# nbedmbed_minipro.net
KiCad netlist of a schematic drawn in EAGLE
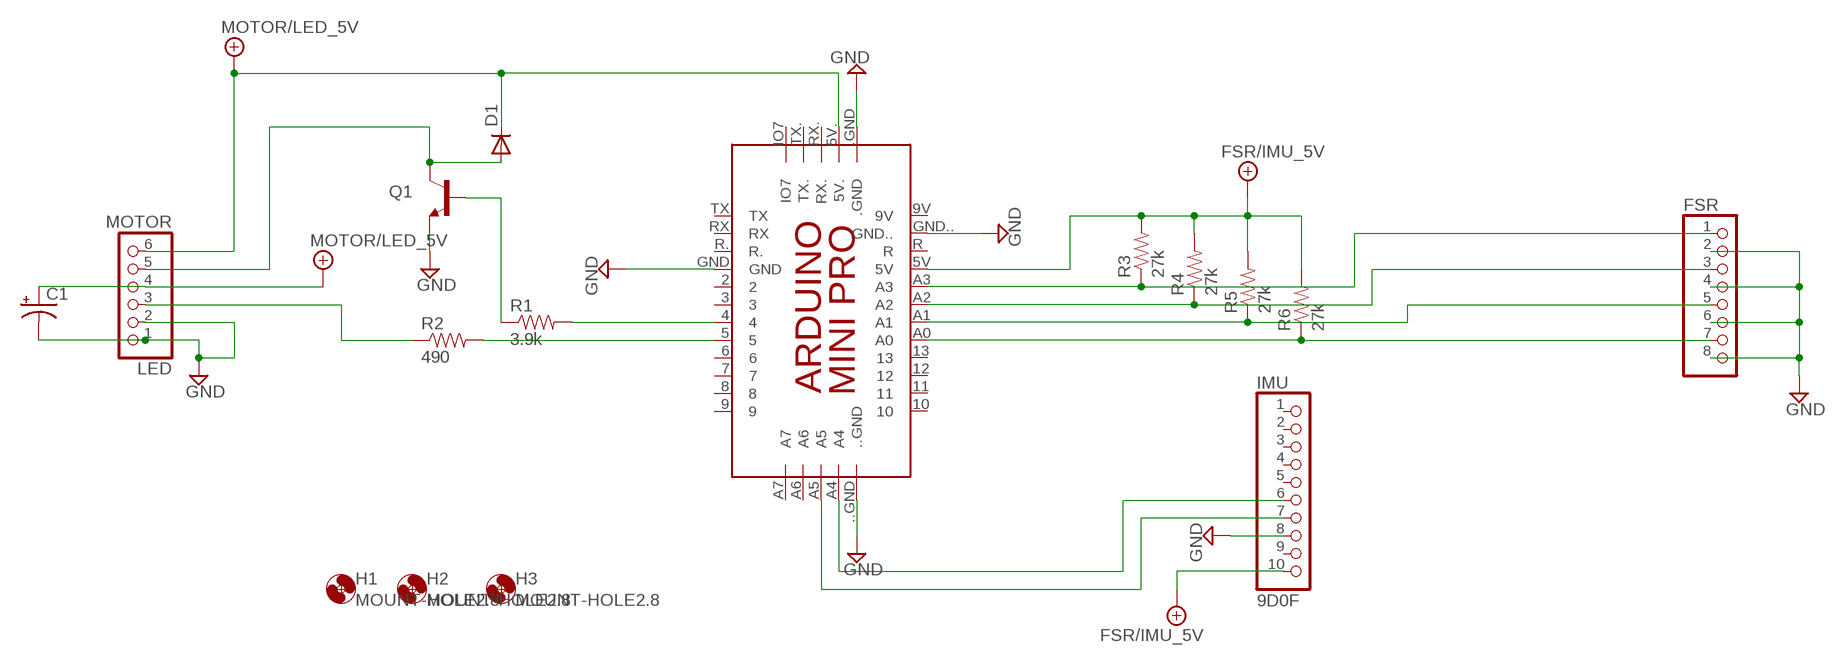
[diagram p0: schematic, sheet 1]

(export (version "E")
  (design (tool "Eeschema 10.0.6"))
  (components
    (comp (ref "C1")
      (value "CAP_POLPTH1")
      (footprint "eagle-import:CPOL-RADIAL-100UF-25V")
      (libsource (lib "eagle-import") (part "CAP_POLPTH1"))
    )
    (comp (ref "D1")
      (value "DIODE1N4148")
      (footprint "eagle-import:DIODE-1N4148")
      (libsource (lib "eagle-import") (part "DIODE1N4148"))
    )
    (comp (ref "FSR")
      (value "PINHD-1X8BIG")
      (footprint "eagle-import:1X08-BIG")
      (libsource (lib "eagle-import") (part "PINHD-1X8BIG"))
    )
    (comp (ref "H1")
      (value "MOUNT-HOLE2.8")
      (footprint "eagle-import:2,8")
      (libsource (lib "eagle-import") (part "MOUNT-HOLE2.8"))
    )
    (comp (ref "H2")
      (value "MOUNT-HOLE2.8")
      (footprint "eagle-import:2,8")
      (libsource (lib "eagle-import") (part "MOUNT-HOLE2.8"))
    )
    (comp (ref "H3")
      (value "MOUNT-HOLE2.8")
      (footprint "eagle-import:2,8")
      (libsource (lib "eagle-import") (part "MOUNT-HOLE2.8"))
    )
    (comp (ref "IMU")
      (value "9D0F")
      (footprint "eagle-import:1X10-BIG")
      (libsource (lib "eagle-import") (part "PINHD-1X10"))
    )
    (comp (ref "LED")
      (value "MOTOR")
      (footprint "eagle-import:1X06-BIG")
      (libsource (lib "eagle-import") (part "PINHD-1X6B"))
    )
    (comp (ref "PCB2")
      (value "ARDUINO_MINI_PRO")
      (footprint "eagle-import:ARDUINO_MINI_PRO")
      (libsource (lib "eagle-import") (part "ARDUINO_MINI_PRO"))
    )
    (comp (ref "Q1")
      (value "TRANSISTOR_NPNTO-92-AMMO")
      (footprint "eagle-import:TO-92-AMMO")
      (libsource (lib "eagle-import") (part "TRANSISTOR_NPNTO-92-AMMO"))
    )
    (comp (ref "R1")
      (value "3.9k")
      (footprint "eagle-import:1_6W-RES")
      (libsource (lib "eagle-import") (part "RESISTORPTH-1/6W"))
    )
    (comp (ref "R2")
      (value "490")
      (footprint "eagle-import:1_6W-RES")
      (libsource (lib "eagle-import") (part "RESISTORPTH-1/6W"))
    )
    (comp (ref "R3")
      (value "27k")
      (footprint "eagle-import:1_6W-RES")
      (libsource (lib "eagle-import") (part "RESISTORPTH-1/6W"))
    )
    (comp (ref "R4")
      (value "27k")
      (footprint "eagle-import:1_6W-RES")
      (libsource (lib "eagle-import") (part "RESISTORPTH-1/6W"))
    )
    (comp (ref "R5")
      (value "27k")
      (footprint "eagle-import:1_6W-RES")
      (libsource (lib "eagle-import") (part "RESISTORPTH-1/6W"))
    )
    (comp (ref "R6")
      (value "27k")
      (footprint "eagle-import:1_6W-RES")
      (libsource (lib "eagle-import") (part "RESISTORPTH-1/6W"))
    )
  )
  (nets
    (net (code "1") (name "FSR{slash}IMU_5V") (class "Default")
      (node (ref "IMU") (pin "10") (pinfunction "10_10") (pintype "passive"))
      (node (ref "PCB2") (pin "5V") (pinfunction "5V_5V") (pintype "bidirectional"))
      (node (ref "R3") (pin "2") (pinfunction "2_2") (pintype "passive"))
      (node (ref "R4") (pin "2") (pinfunction "2_2") (pintype "passive"))
      (node (ref "R5") (pin "2") (pinfunction "2_2") (pintype "passive"))
      (node (ref "R6") (pin "2") (pinfunction "2_2") (pintype "passive"))
    )
    (net (code "2") (name "GND") (class "Default")
      (node (ref "C1") (pin "2") (pinfunction "-_2") (pintype "passive"))
      (node (ref "FSR") (pin "2") (pinfunction "2_2") (pintype "passive"))
      (node (ref "FSR") (pin "4") (pinfunction "4_4") (pintype "passive"))
      (node (ref "FSR") (pin "6") (pinfunction "6_6") (pintype "passive"))
      (node (ref "FSR") (pin "8") (pinfunction "8_8") (pintype "passive"))
      (node (ref "IMU") (pin "8") (pinfunction "8_8") (pintype "passive"))
      (node (ref "LED") (pin "1") (pinfunction "1_1") (pintype "passive"))
      (node (ref "LED") (pin "2") (pinfunction "2_2") (pintype "passive"))
      (node (ref "PCB2") (pin "..GND") (pinfunction "..GND_..GND") (pintype "bidirectional"))
      (node (ref "PCB2") (pin ".GND") (pinfunction ".GND_.GND") (pintype "bidirectional"))
      (node (ref "PCB2") (pin "GND") (pinfunction "GND_GND") (pintype "bidirectional"))
      (node (ref "PCB2") (pin "GND..") (pinfunction "GND.._GND..") (pintype "bidirectional"))
      (node (ref "Q1") (pin "1") (pinfunction "E_1") (pintype "passive"))
    )
    (net (code "3") (name "MOTOR{slash}LED_5V") (class "Default")
      (node (ref "C1") (pin "1") (pinfunction "+_1") (pintype "passive"))
      (node (ref "D1") (pin "C") (pinfunction "C_C") (pintype "passive"))
      (node (ref "LED") (pin "4") (pinfunction "4_4") (pintype "passive"))
      (node (ref "LED") (pin "6") (pinfunction "6_6") (pintype "passive"))
      (node (ref "PCB2") (pin "5V.") (pinfunction "5V._5V.") (pintype "bidirectional"))
    )
    (net (code "4") (name "Net-(FSR-Pad1)") (class "Default")
      (node (ref "FSR") (pin "1") (pinfunction "1_1") (pintype "passive"))
      (node (ref "PCB2") (pin "A3") (pinfunction "A3_A3") (pintype "bidirectional"))
      (node (ref "R3") (pin "1") (pinfunction "1_1") (pintype "passive"))
    )
    (net (code "5") (name "Net-(FSR-Pad3)") (class "Default")
      (node (ref "FSR") (pin "3") (pinfunction "3_3") (pintype "passive"))
      (node (ref "PCB2") (pin "A2") (pinfunction "A2_A2") (pintype "bidirectional"))
      (node (ref "R4") (pin "1") (pinfunction "1_1") (pintype "passive"))
    )
    (net (code "6") (name "Net-(FSR-Pad5)") (class "Default")
      (node (ref "FSR") (pin "5") (pinfunction "5_5") (pintype "passive"))
      (node (ref "PCB2") (pin "A1") (pinfunction "A1_A1") (pintype "bidirectional"))
      (node (ref "R5") (pin "1") (pinfunction "1_1") (pintype "passive"))
    )
    (net (code "7") (name "Net-(FSR-Pad7)") (class "Default")
      (node (ref "FSR") (pin "7") (pinfunction "7_7") (pintype "passive"))
      (node (ref "PCB2") (pin "A0") (pinfunction "A0_A0") (pintype "bidirectional"))
      (node (ref "R6") (pin "1") (pinfunction "1_1") (pintype "passive"))
    )
    (net (code "8") (name "Net-(IMU-Pad6)") (class "Default")
      (node (ref "IMU") (pin "6") (pinfunction "6_6") (pintype "passive"))
      (node (ref "PCB2") (pin "A4") (pinfunction "A4_A4") (pintype "bidirectional"))
    )
    (net (code "9") (name "Net-(IMU-Pad7)") (class "Default")
      (node (ref "IMU") (pin "7") (pinfunction "7_7") (pintype "passive"))
      (node (ref "PCB2") (pin "A5") (pinfunction "A5_A5") (pintype "bidirectional"))
    )
    (net (code "10") (name "Net-(LED-Pad3)") (class "Default")
      (node (ref "LED") (pin "3") (pinfunction "3_3") (pintype "passive"))
      (node (ref "R2") (pin "1") (pinfunction "1_1") (pintype "passive"))
    )
    (net (code "11") (name "Net-(PCB2-Pad4)") (class "Default")
      (node (ref "PCB2") (pin "4") (pinfunction "4_4") (pintype "bidirectional"))
      (node (ref "R1") (pin "2") (pinfunction "2_2") (pintype "passive"))
    )
    (net (code "12") (name "Net-(PCB2-Pad5)") (class "Default")
      (node (ref "PCB2") (pin "5") (pinfunction "5_5") (pintype "bidirectional"))
      (node (ref "R2") (pin "2") (pinfunction "2_2") (pintype "passive"))
    )
    (net (code "13") (name "Net-(Q1-B)") (class "Default")
      (node (ref "Q1") (pin "2") (pinfunction "B_2") (pintype "passive"))
      (node (ref "R1") (pin "1") (pinfunction "1_1") (pintype "passive"))
    )
    (net (code "14") (name "Net-(Q1-C)") (class "Default")
      (node (ref "D1") (pin "A") (pinfunction "A_A") (pintype "passive"))
      (node (ref "LED") (pin "5") (pinfunction "5_5") (pintype "passive"))
      (node (ref "Q1") (pin "3") (pinfunction "C_3") (pintype "passive"))
    )
    (net (code "15") (name "unconnected-(IMU-Pad1)") (class "Default")
      (node (ref "IMU") (pin "1") (pinfunction "1_1") (pintype "passive"))
    )
    (net (code "16") (name "unconnected-(IMU-Pad2)") (class "Default")
      (node (ref "IMU") (pin "2") (pinfunction "2_2") (pintype "passive"))
    )
    (net (code "17") (name "unconnected-(IMU-Pad3)") (class "Default")
      (node (ref "IMU") (pin "3") (pinfunction "3_3") (pintype "passive"))
    )
    (net (code "18") (name "unconnected-(IMU-Pad4)") (class "Default")
      (node (ref "IMU") (pin "4") (pinfunction "4_4") (pintype "passive"))
    )
    (net (code "19") (name "unconnected-(IMU-Pad5)") (class "Default")
      (node (ref "IMU") (pin "5") (pinfunction "5_5") (pintype "passive"))
    )
    (net (code "20") (name "unconnected-(IMU-Pad9)") (class "Default")
      (node (ref "IMU") (pin "9") (pinfunction "9_9") (pintype "passive"))
    )
    (net (code "21") (name "unconnected-(PCB2-Pad2)") (class "Default")
      (node (ref "PCB2") (pin "2") (pinfunction "2_2") (pintype "bidirectional"))
    )
    (net (code "22") (name "unconnected-(PCB2-Pad3)") (class "Default")
      (node (ref "PCB2") (pin "3") (pinfunction "3_3") (pintype "bidirectional"))
    )
    (net (code "23") (name "unconnected-(PCB2-Pad6)") (class "Default")
      (node (ref "PCB2") (pin "6") (pinfunction "6_6") (pintype "bidirectional"))
    )
    (net (code "24") (name "unconnected-(PCB2-Pad7)") (class "Default")
      (node (ref "PCB2") (pin "7") (pinfunction "7_7") (pintype "bidirectional"))
    )
    (net (code "25") (name "unconnected-(PCB2-Pad8)") (class "Default")
      (node (ref "PCB2") (pin "8") (pinfunction "8_8") (pintype "bidirectional"))
    )
    (net (code "26") (name "unconnected-(PCB2-Pad9)") (class "Default")
      (node (ref "PCB2") (pin "9") (pinfunction "9_9") (pintype "bidirectional"))
    )
    (net (code "27") (name "unconnected-(PCB2-Pad9V)") (class "Default")
      (node (ref "PCB2") (pin "9V") (pinfunction "9V_9V") (pintype "bidirectional"))
    )
    (net (code "28") (name "unconnected-(PCB2-Pad10)") (class "Default")
      (node (ref "PCB2") (pin "10") (pinfunction "10_10") (pintype "bidirectional"))
    )
    (net (code "29") (name "unconnected-(PCB2-Pad11)") (class "Default")
      (node (ref "PCB2") (pin "11") (pinfunction "11_11") (pintype "bidirectional"))
    )
    (net (code "30") (name "unconnected-(PCB2-Pad12)") (class "Default")
      (node (ref "PCB2") (pin "12") (pinfunction "12_12") (pintype "bidirectional"))
    )
    (net (code "31") (name "unconnected-(PCB2-Pad13)") (class "Default")
      (node (ref "PCB2") (pin "13") (pinfunction "13_13") (pintype "bidirectional"))
    )
    (net (code "32") (name "unconnected-(PCB2-PadA6)") (class "Default")
      (node (ref "PCB2") (pin "A6") (pinfunction "A6_A6") (pintype "bidirectional"))
    )
    (net (code "33") (name "unconnected-(PCB2-PadA7)") (class "Default")
      (node (ref "PCB2") (pin "A7") (pinfunction "A7_A7") (pintype "bidirectional"))
    )
    (net (code "34") (name "unconnected-(PCB2-PadIO7)") (class "Default")
      (node (ref "PCB2") (pin "IO7") (pinfunction "IO7_IO7") (pintype "bidirectional"))
    )
    (net (code "35") (name "unconnected-(PCB2-PadR)") (class "Default")
      (node (ref "PCB2") (pin "R") (pinfunction "R_R") (pintype "bidirectional"))
    )
    (net (code "36") (name "unconnected-(PCB2-PadR.)") (class "Default")
      (node (ref "PCB2") (pin "R.") (pinfunction "R._R.") (pintype "bidirectional"))
    )
    (net (code "37") (name "unconnected-(PCB2-PadRX)") (class "Default")
      (node (ref "PCB2") (pin "RX") (pinfunction "RX_RX") (pintype "bidirectional"))
    )
    (net (code "38") (name "unconnected-(PCB2-PadRX.)") (class "Default")
      (node (ref "PCB2") (pin "RX.") (pinfunction "RX._RX.") (pintype "bidirectional"))
    )
    (net (code "39") (name "unconnected-(PCB2-PadTX)") (class "Default")
      (node (ref "PCB2") (pin "TX") (pinfunction "TX_TX") (pintype "bidirectional"))
    )
    (net (code "40") (name "unconnected-(PCB2-PadTX.)") (class "Default")
      (node (ref "PCB2") (pin "TX.") (pinfunction "TX._TX.") (pintype "bidirectional"))
    )
  )
)
